# cubo.net
KiCad netlist of a schematic drawn in EAGLE
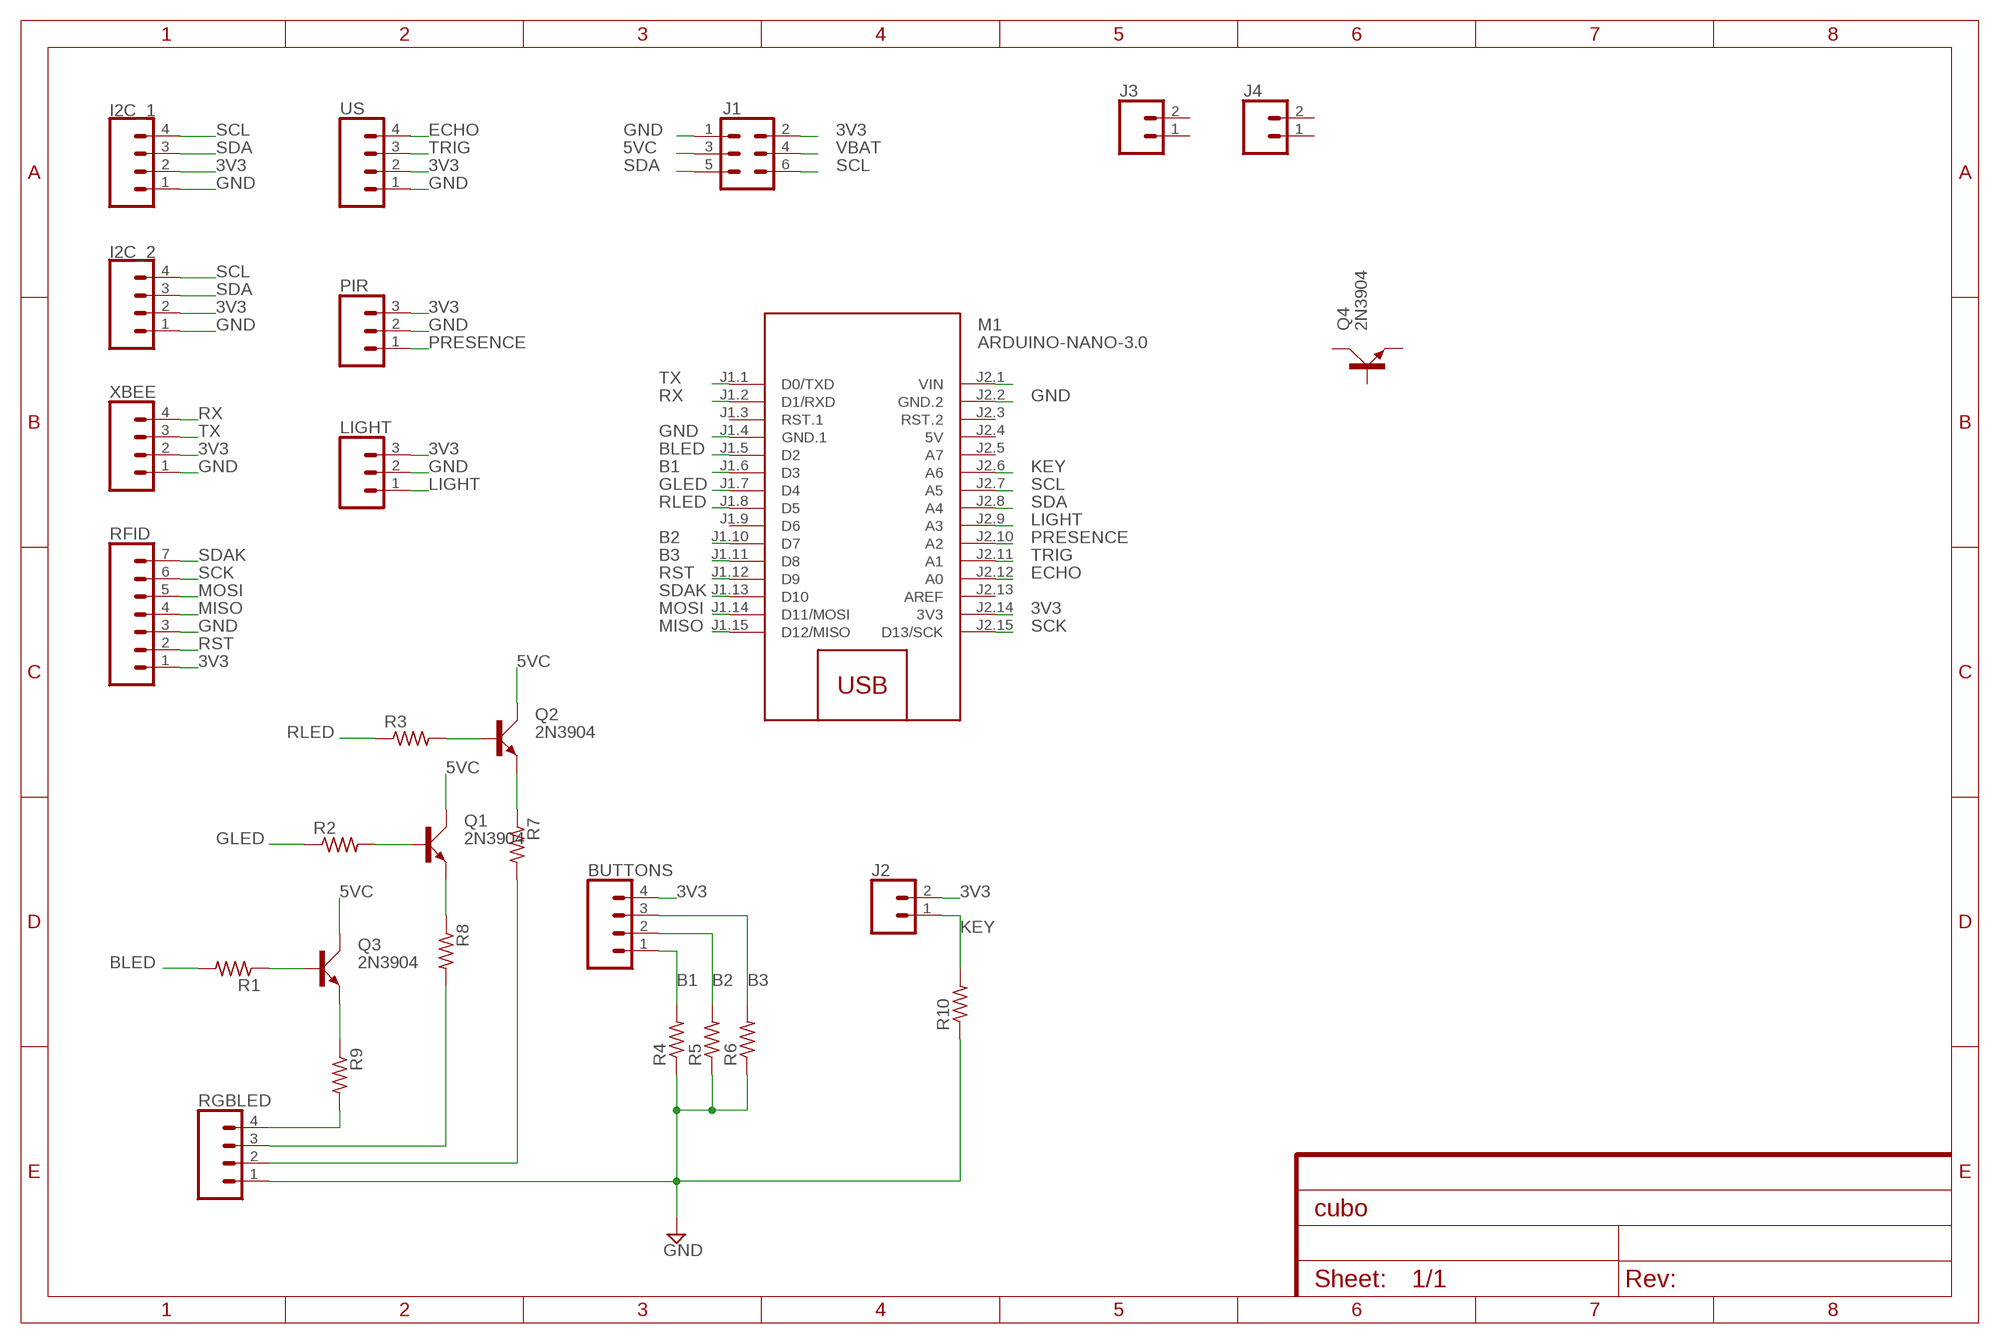
[diagram p0: schematic, sheet 1]

(export (version "E")
  (design (tool "Eeschema 10.0.6"))
  (components
    (comp (ref "BUTTONS")
      (value "CONN_04JST-PTH-VERT")
      (footprint "eagle-import:JST-4-PTH-VERT")
      (libsource (lib "eagle-import") (part "CONN_04JST-PTH-VERT"))
    )
    (comp (ref "I2C_1")
      (value "CONN_04JST-PTH-VERT")
      (footprint "eagle-import:JST-4-PTH-VERT")
      (libsource (lib "eagle-import") (part "CONN_04JST-PTH-VERT"))
    )
    (comp (ref "I2C_2")
      (value "CONN_04JST-PTH-VERT")
      (footprint "eagle-import:JST-4-PTH-VERT")
      (libsource (lib "eagle-import") (part "CONN_04JST-PTH-VERT"))
    )
    (comp (ref "J1")
      (value "CONN_03X2SHROUD")
      (footprint "eagle-import:2X3-SHROUDED")
      (libsource (lib "eagle-import") (part "CONN_03X2SHROUD"))
    )
    (comp (ref "J2")
      (value "CONN_02POLAR_LOCK")
      (footprint "eagle-import:MOLEX-1X2_LOCK")
      (libsource (lib "eagle-import") (part "CONN_02POLAR_LOCK"))
    )
    (comp (ref "J3")
      (value "CONN_02POLAR_LOCK")
      (footprint "eagle-import:MOLEX-1X2_LOCK")
      (libsource (lib "eagle-import") (part "CONN_02POLAR_LOCK"))
    )
    (comp (ref "J4")
      (value "CONN_02POLAR_LOCK")
      (footprint "eagle-import:MOLEX-1X2_LOCK")
      (libsource (lib "eagle-import") (part "CONN_02POLAR_LOCK"))
    )
    (comp (ref "LIGHT")
      (value "CONN_03JST-PTH-VERT")
      (footprint "eagle-import:JST-3-PTH-VERT")
      (libsource (lib "eagle-import") (part "CONN_03JST-PTH-VERT"))
    )
    (comp (ref "M1")
      (value "ARDUINO-NANO-3.0")
      (footprint "eagle-import:ARDUINO-NANO-3.0")
      (libsource (lib "eagle-import") (part "ARDUINO-NANO-3.0"))
    )
    (comp (ref "PIR")
      (value "CONN_03JST-PTH-VERT")
      (footprint "eagle-import:JST-3-PTH-VERT")
      (libsource (lib "eagle-import") (part "CONN_03JST-PTH-VERT"))
    )
    (comp (ref "Q1")
      (value "2N3904")
      (footprint "eagle-import:TO92D")
      (libsource (lib "eagle-import") (part "2N3904"))
    )
    (comp (ref "Q2")
      (value "2N3904")
      (footprint "eagle-import:TO92D")
      (libsource (lib "eagle-import") (part "2N3904"))
    )
    (comp (ref "Q3")
      (value "2N3904")
      (footprint "eagle-import:TO92D")
      (libsource (lib "eagle-import") (part "2N3904"))
    )
    (comp (ref "Q4")
      (value "2N3904")
      (footprint "eagle-import:TO92D")
      (libsource (lib "eagle-import") (part "2N3904"))
    )
    (comp (ref "R1")
      (value "R-US_0207/10")
      (footprint "eagle-import:0207_10")
      (libsource (lib "eagle-import") (part "R-US_0207/10"))
    )
    (comp (ref "R2")
      (value "R-US_0207/10")
      (footprint "eagle-import:0207_10")
      (libsource (lib "eagle-import") (part "R-US_0207/10"))
    )
    (comp (ref "R3")
      (value "R-US_0207/10")
      (footprint "eagle-import:0207_10")
      (libsource (lib "eagle-import") (part "R-US_0207/10"))
    )
    (comp (ref "R4")
      (value "R-US_0207/10")
      (footprint "eagle-import:0207_10")
      (libsource (lib "eagle-import") (part "R-US_0207/10"))
    )
    (comp (ref "R5")
      (value "R-US_0207/10")
      (footprint "eagle-import:0207_10")
      (libsource (lib "eagle-import") (part "R-US_0207/10"))
    )
    (comp (ref "R6")
      (value "R-US_0207/10")
      (footprint "eagle-import:0207_10")
      (libsource (lib "eagle-import") (part "R-US_0207/10"))
    )
    (comp (ref "R7")
      (value "R-US_0207/10")
      (footprint "eagle-import:0207_10")
      (libsource (lib "eagle-import") (part "R-US_0207/10"))
    )
    (comp (ref "R8")
      (value "R-US_0207/10")
      (footprint "eagle-import:0207_10")
      (libsource (lib "eagle-import") (part "R-US_0207/10"))
    )
    (comp (ref "R9")
      (value "R-US_0207/10")
      (footprint "eagle-import:0207_10")
      (libsource (lib "eagle-import") (part "R-US_0207/10"))
    )
    (comp (ref "R10")
      (value "R-US_0207/10")
      (footprint "eagle-import:0207_10")
      (libsource (lib "eagle-import") (part "R-US_0207/10"))
    )
    (comp (ref "RFID")
      (value "CONN_07")
      (footprint "eagle-import:1X07")
      (libsource (lib "eagle-import") (part "CONN_07"))
    )
    (comp (ref "RGBLED")
      (value "CONN_04JST-PTH-VERT")
      (footprint "eagle-import:JST-4-PTH-VERT")
      (libsource (lib "eagle-import") (part "CONN_04JST-PTH-VERT"))
    )
    (comp (ref "US")
      (value "CONN_04JST-PTH-VERT")
      (footprint "eagle-import:JST-4-PTH-VERT")
      (libsource (lib "eagle-import") (part "CONN_04JST-PTH-VERT"))
    )
    (comp (ref "XBEE")
      (value "CONN_04JST-PTH-VERT")
      (footprint "eagle-import:JST-4-PTH-VERT")
      (libsource (lib "eagle-import") (part "CONN_04JST-PTH-VERT"))
    )
  )
  (nets
    (net (code "1") (name "/3V3") (class "Default")
      (node (ref "BUTTONS") (pin "4") (pinfunction "4_4") (pintype "passive"))
      (node (ref "I2C_1") (pin "2") (pinfunction "2_2") (pintype "passive"))
      (node (ref "I2C_2") (pin "2") (pinfunction "2_2") (pintype "passive"))
      (node (ref "J1") (pin "2") (pinfunction "2_2") (pintype "bidirectional"))
      (node (ref "J2") (pin "2") (pinfunction "2_2") (pintype "passive"))
      (node (ref "LIGHT") (pin "3") (pinfunction "3_3") (pintype "passive"))
      (node (ref "M1") (pin "J2.14") (pinfunction "3V3_J2.14") (pintype "power_in"))
      (node (ref "PIR") (pin "3") (pinfunction "3_3") (pintype "passive"))
      (node (ref "RFID") (pin "1") (pinfunction "1_1") (pintype "passive"))
      (node (ref "US") (pin "2") (pinfunction "2_2") (pintype "passive"))
      (node (ref "XBEE") (pin "2") (pinfunction "2_2") (pintype "passive"))
    )
    (net (code "2") (name "/5V") (class "Default")
      (node (ref "M1") (pin "J2.4") (pinfunction "5V_J2.4") (pintype "power_in"))
    )
    (net (code "3") (name "/5VC") (class "Default")
      (node (ref "J1") (pin "3") (pinfunction "3_3") (pintype "bidirectional"))
      (node (ref "Q1") (pin "C") (pinfunction "C_C") (pintype "passive"))
      (node (ref "Q2") (pin "C") (pinfunction "C_C") (pintype "passive"))
      (node (ref "Q3") (pin "C") (pinfunction "C_C") (pintype "passive"))
    )
    (net (code "4") (name "/B1") (class "Default")
      (node (ref "BUTTONS") (pin "1") (pinfunction "1_1") (pintype "passive"))
      (node (ref "M1") (pin "J1.6") (pinfunction "D3_J1.6") (pintype "bidirectional"))
      (node (ref "R4") (pin "2") (pinfunction "2_2") (pintype "passive"))
    )
    (net (code "5") (name "/B2") (class "Default")
      (node (ref "BUTTONS") (pin "2") (pinfunction "2_2") (pintype "passive"))
      (node (ref "M1") (pin "J1.10") (pinfunction "D7_J1.10") (pintype "bidirectional"))
      (node (ref "R5") (pin "2") (pinfunction "2_2") (pintype "passive"))
    )
    (net (code "6") (name "/B3") (class "Default")
      (node (ref "BUTTONS") (pin "3") (pinfunction "3_3") (pintype "passive"))
      (node (ref "M1") (pin "J1.11") (pinfunction "D8_J1.11") (pintype "bidirectional"))
      (node (ref "R6") (pin "2") (pinfunction "2_2") (pintype "passive"))
    )
    (net (code "7") (name "/BLED") (class "Default")
      (node (ref "M1") (pin "J1.5") (pinfunction "D2_J1.5") (pintype "bidirectional"))
      (node (ref "R1") (pin "2") (pinfunction "2_2") (pintype "passive"))
    )
    (net (code "8") (name "/ECHO") (class "Default")
      (node (ref "M1") (pin "J2.12") (pinfunction "A0_J2.12") (pintype "bidirectional"))
      (node (ref "US") (pin "4") (pinfunction "4_4") (pintype "passive"))
    )
    (net (code "9") (name "/GLED") (class "Default")
      (node (ref "M1") (pin "J1.7") (pinfunction "D4_J1.7") (pintype "bidirectional"))
      (node (ref "R2") (pin "1") (pinfunction "1_1") (pintype "passive"))
    )
    (net (code "10") (name "/KEY") (class "Default")
      (node (ref "J2") (pin "1") (pinfunction "1_1") (pintype "passive"))
      (node (ref "M1") (pin "J2.6") (pinfunction "A6_J2.6") (pintype "bidirectional"))
      (node (ref "R10") (pin "2") (pinfunction "2_2") (pintype "passive"))
    )
    (net (code "11") (name "/LIGHT") (class "Default")
      (node (ref "LIGHT") (pin "1") (pinfunction "1_1") (pintype "passive"))
      (node (ref "M1") (pin "J2.9") (pinfunction "A3_J2.9") (pintype "bidirectional"))
    )
    (net (code "12") (name "/MISO") (class "Default")
      (node (ref "M1") (pin "J1.15") (pinfunction "D12/MISO_J1.15") (pintype "bidirectional"))
      (node (ref "RFID") (pin "4") (pinfunction "4_4") (pintype "passive"))
    )
    (net (code "13") (name "/MOSI") (class "Default")
      (node (ref "M1") (pin "J1.14") (pinfunction "D11/MOSI_J1.14") (pintype "bidirectional"))
      (node (ref "RFID") (pin "5") (pinfunction "5_5") (pintype "passive"))
    )
    (net (code "14") (name "/PRESENCE") (class "Default")
      (node (ref "M1") (pin "J2.10") (pinfunction "A2_J2.10") (pintype "bidirectional"))
      (node (ref "PIR") (pin "1") (pinfunction "1_1") (pintype "passive"))
    )
    (net (code "15") (name "/RLED") (class "Default")
      (node (ref "M1") (pin "J1.8") (pinfunction "D5_J1.8") (pintype "bidirectional"))
      (node (ref "R3") (pin "1") (pinfunction "1_1") (pintype "passive"))
    )
    (net (code "16") (name "/RST") (class "Default")
      (node (ref "M1") (pin "J1.12") (pinfunction "D9_J1.12") (pintype "bidirectional"))
      (node (ref "RFID") (pin "2") (pinfunction "2_2") (pintype "passive"))
    )
    (net (code "17") (name "/RX") (class "Default")
      (node (ref "M1") (pin "J1.2") (pinfunction "D1/RXD_J1.2") (pintype "bidirectional"))
      (node (ref "XBEE") (pin "4") (pinfunction "4_4") (pintype "passive"))
    )
    (net (code "18") (name "/SCK") (class "Default")
      (node (ref "M1") (pin "J2.15") (pinfunction "D13/SCK_J2.15") (pintype "bidirectional"))
      (node (ref "RFID") (pin "6") (pinfunction "6_6") (pintype "passive"))
    )
    (net (code "19") (name "/SCL") (class "Default")
      (node (ref "I2C_1") (pin "4") (pinfunction "4_4") (pintype "passive"))
      (node (ref "I2C_2") (pin "4") (pinfunction "4_4") (pintype "passive"))
      (node (ref "J1") (pin "6") (pinfunction "6_6") (pintype "bidirectional"))
      (node (ref "M1") (pin "J2.7") (pinfunction "A5_J2.7") (pintype "bidirectional"))
    )
    (net (code "20") (name "/SDA") (class "Default")
      (node (ref "I2C_1") (pin "3") (pinfunction "3_3") (pintype "passive"))
      (node (ref "I2C_2") (pin "3") (pinfunction "3_3") (pintype "passive"))
      (node (ref "J1") (pin "5") (pinfunction "5_5") (pintype "bidirectional"))
      (node (ref "M1") (pin "J2.8") (pinfunction "A4_J2.8") (pintype "bidirectional"))
    )
    (net (code "21") (name "/SDAK") (class "Default")
      (node (ref "M1") (pin "J1.13") (pinfunction "D10_J1.13") (pintype "bidirectional"))
      (node (ref "RFID") (pin "7") (pinfunction "7_7") (pintype "passive"))
    )
    (net (code "22") (name "/TRIG") (class "Default")
      (node (ref "M1") (pin "J2.11") (pinfunction "A1_J2.11") (pintype "bidirectional"))
      (node (ref "US") (pin "3") (pinfunction "3_3") (pintype "passive"))
    )
    (net (code "23") (name "/TX") (class "Default")
      (node (ref "M1") (pin "J1.1") (pinfunction "D0/TXD_J1.1") (pintype "bidirectional"))
      (node (ref "XBEE") (pin "3") (pinfunction "3_3") (pintype "passive"))
    )
    (net (code "24") (name "/VBAT") (class "Default")
      (node (ref "J1") (pin "4") (pinfunction "4_4") (pintype "bidirectional"))
    )
    (net (code "25") (name "GND") (class "Default")
      (node (ref "I2C_1") (pin "1") (pinfunction "1_1") (pintype "passive"))
      (node (ref "I2C_2") (pin "1") (pinfunction "1_1") (pintype "passive"))
      (node (ref "J1") (pin "1") (pinfunction "1_1") (pintype "bidirectional"))
      (node (ref "LIGHT") (pin "2") (pinfunction "2_2") (pintype "passive"))
      (node (ref "M1") (pin "J1.4") (pinfunction "GND.1_J1.4") (pintype "power_in"))
      (node (ref "M1") (pin "J2.2") (pinfunction "GND.2_J2.2") (pintype "power_in"))
      (node (ref "PIR") (pin "2") (pinfunction "2_2") (pintype "passive"))
      (node (ref "R10") (pin "1") (pinfunction "1_1") (pintype "passive"))
      (node (ref "R4") (pin "1") (pinfunction "1_1") (pintype "passive"))
      (node (ref "R5") (pin "1") (pinfunction "1_1") (pintype "passive"))
      (node (ref "R6") (pin "1") (pinfunction "1_1") (pintype "passive"))
      (node (ref "RFID") (pin "3") (pinfunction "3_3") (pintype "passive"))
      (node (ref "RGBLED") (pin "1") (pinfunction "1_1") (pintype "passive"))
      (node (ref "US") (pin "1") (pinfunction "1_1") (pintype "passive"))
      (node (ref "XBEE") (pin "1") (pinfunction "1_1") (pintype "passive"))
    )
    (net (code "26") (name "Net-(Q1-PadB)") (class "Default")
      (node (ref "Q1") (pin "B") (pinfunction "B_B") (pintype "passive"))
      (node (ref "R2") (pin "2") (pinfunction "2_2") (pintype "passive"))
    )
    (net (code "27") (name "Net-(Q1-PadE)") (class "Default")
      (node (ref "Q1") (pin "E") (pinfunction "E_E") (pintype "passive"))
      (node (ref "R8") (pin "1") (pinfunction "1_1") (pintype "passive"))
    )
    (net (code "28") (name "Net-(Q2-PadB)") (class "Default")
      (node (ref "Q2") (pin "B") (pinfunction "B_B") (pintype "passive"))
      (node (ref "R3") (pin "2") (pinfunction "2_2") (pintype "passive"))
    )
    (net (code "29") (name "Net-(Q2-PadE)") (class "Default")
      (node (ref "Q2") (pin "E") (pinfunction "E_E") (pintype "passive"))
      (node (ref "R7") (pin "1") (pinfunction "1_1") (pintype "passive"))
    )
    (net (code "30") (name "Net-(Q3-PadB)") (class "Default")
      (node (ref "Q3") (pin "B") (pinfunction "B_B") (pintype "passive"))
      (node (ref "R1") (pin "1") (pinfunction "1_1") (pintype "passive"))
    )
    (net (code "31") (name "Net-(Q3-PadE)") (class "Default")
      (node (ref "Q3") (pin "E") (pinfunction "E_E") (pintype "passive"))
      (node (ref "R9") (pin "1") (pinfunction "1_1") (pintype "passive"))
    )
    (net (code "32") (name "Net-(R7-Pad2)") (class "Default")
      (node (ref "R7") (pin "2") (pinfunction "2_2") (pintype "passive"))
      (node (ref "RGBLED") (pin "2") (pinfunction "2_2") (pintype "passive"))
    )
    (net (code "33") (name "Net-(R8-Pad2)") (class "Default")
      (node (ref "R8") (pin "2") (pinfunction "2_2") (pintype "passive"))
      (node (ref "RGBLED") (pin "3") (pinfunction "3_3") (pintype "passive"))
    )
    (net (code "34") (name "Net-(R9-Pad2)") (class "Default")
      (node (ref "R9") (pin "2") (pinfunction "2_2") (pintype "passive"))
      (node (ref "RGBLED") (pin "4") (pinfunction "4_4") (pintype "passive"))
    )
    (net (code "35") (name "unconnected-(J3-Pad1)") (class "Default")
      (node (ref "J3") (pin "1") (pinfunction "1_1") (pintype "passive"))
    )
    (net (code "36") (name "unconnected-(J3-Pad2)") (class "Default")
      (node (ref "J3") (pin "2") (pinfunction "2_2") (pintype "passive"))
    )
    (net (code "37") (name "unconnected-(J4-Pad1)") (class "Default")
      (node (ref "J4") (pin "1") (pinfunction "1_1") (pintype "passive"))
    )
    (net (code "38") (name "unconnected-(J4-Pad2)") (class "Default")
      (node (ref "J4") (pin "2") (pinfunction "2_2") (pintype "passive"))
    )
    (net (code "39") (name "unconnected-(M1-A7-PadJ2.5)") (class "Default")
      (node (ref "M1") (pin "J2.5") (pinfunction "A7_J2.5") (pintype "bidirectional"))
    )
    (net (code "40") (name "unconnected-(M1-AREF-PadJ2.13)") (class "Default")
      (node (ref "M1") (pin "J2.13") (pinfunction "AREF_J2.13") (pintype "bidirectional"))
    )
    (net (code "41") (name "unconnected-(M1-D6-PadJ1.9)") (class "Default")
      (node (ref "M1") (pin "J1.9") (pinfunction "D6_J1.9") (pintype "bidirectional"))
    )
    (net (code "42") (name "unconnected-(M1-RST.1-PadJ1.3)") (class "Default")
      (node (ref "M1") (pin "J1.3") (pinfunction "RST.1_J1.3") (pintype "bidirectional"))
    )
    (net (code "43") (name "unconnected-(M1-RST.2-PadJ2.3)") (class "Default")
      (node (ref "M1") (pin "J2.3") (pinfunction "RST.2_J2.3") (pintype "bidirectional"))
    )
    (net (code "44") (name "unconnected-(M1-VIN-PadJ2.1)") (class "Default")
      (node (ref "M1") (pin "J2.1") (pinfunction "VIN_J2.1") (pintype "power_in"))
    )
    (net (code "45") (name "unconnected-(Q4-PadB)") (class "Default")
      (node (ref "Q4") (pin "B") (pinfunction "B_B") (pintype "passive"))
    )
    (net (code "46") (name "unconnected-(Q4-PadC)") (class "Default")
      (node (ref "Q4") (pin "C") (pinfunction "C_C") (pintype "passive"))
    )
    (net (code "47") (name "unconnected-(Q4-PadE)") (class "Default")
      (node (ref "Q4") (pin "E") (pinfunction "E_E") (pintype "passive"))
    )
  )
)
